# MultiChannelLdc2.net
KiCad netlist of a schematic drawn in Altium Designer
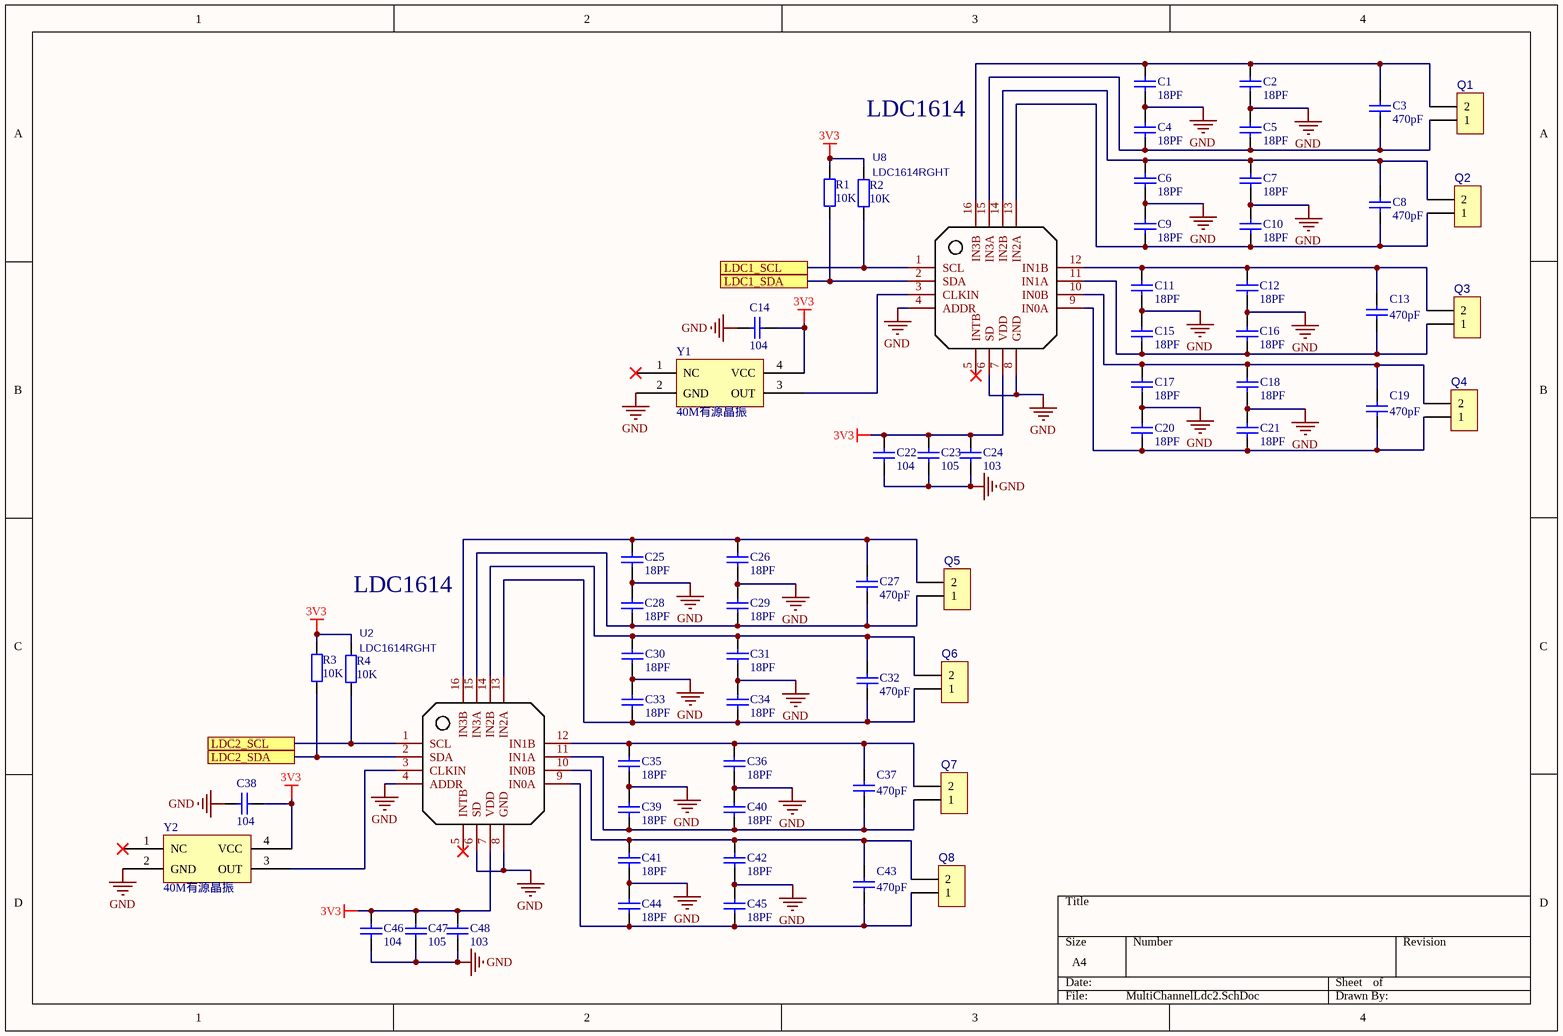
[diagram p0: MultiChannelLdc2.SchDoc]

(export (version "E")
  (design (tool "Eeschema 10.0.6"))
  (components
    (comp (ref "C1")
      (value "18PF")
      (footprint "C0603_L")
      (description "Capacitor")
      (fields (field (name "PUBLISHER") "Altium Limited"))
      (libsource (lib "STM32F103C8T6") (part "Cap"))
    )
    (comp (ref "C2")
      (value "18PF")
      (footprint "C0603_L")
      (description "Capacitor")
      (fields (field (name "PUBLISHER") "Altium Limited"))
      (libsource (lib "STM32F103C8T6") (part "Cap"))
    )
    (comp (ref "C3")
      (value "470pF")
      (footprint "C0603_L")
      (description "Capacitor")
      (fields (field (name "PUBLISHER") "Altium Limited"))
      (libsource (lib "STM32F103C8T6") (part "Cap"))
    )
    (comp (ref "C4")
      (value "18PF")
      (footprint "C0603_L")
      (description "Capacitor")
      (fields (field (name "PUBLISHER") "Altium Limited"))
      (libsource (lib "STM32F103C8T6") (part "Cap"))
    )
    (comp (ref "C5")
      (value "18PF")
      (footprint "C0603_L")
      (description "Capacitor")
      (fields (field (name "PUBLISHER") "Altium Limited"))
      (libsource (lib "STM32F103C8T6") (part "Cap"))
    )
    (comp (ref "C6")
      (value "18PF")
      (footprint "C0603_L")
      (description "Capacitor")
      (fields (field (name "PUBLISHER") "Altium Limited"))
      (libsource (lib "STM32F103C8T6") (part "Cap"))
    )
    (comp (ref "C7")
      (value "18PF")
      (footprint "C0603_L")
      (description "Capacitor")
      (fields (field (name "PUBLISHER") "Altium Limited"))
      (libsource (lib "STM32F103C8T6") (part "Cap"))
    )
    (comp (ref "C8")
      (value "470pF")
      (footprint "C0603_L")
      (description "Capacitor")
      (fields (field (name "PUBLISHER") "Altium Limited"))
      (libsource (lib "STM32F103C8T6") (part "Cap"))
    )
    (comp (ref "C9")
      (value "18PF")
      (footprint "C0603_L")
      (description "Capacitor")
      (fields (field (name "PUBLISHER") "Altium Limited"))
      (libsource (lib "STM32F103C8T6") (part "Cap"))
    )
    (comp (ref "C10")
      (value "18PF")
      (footprint "C0603_L")
      (description "Capacitor")
      (fields (field (name "PUBLISHER") "Altium Limited"))
      (libsource (lib "STM32F103C8T6") (part "Cap"))
    )
    (comp (ref "C11")
      (value "18PF")
      (footprint "C0603_L")
      (description "Capacitor")
      (fields (field (name "PUBLISHER") "Altium Limited"))
      (libsource (lib "STM32F103C8T6") (part "Cap"))
    )
    (comp (ref "C12")
      (value "18PF")
      (footprint "C0603_L")
      (description "Capacitor")
      (fields (field (name "PUBLISHER") "Altium Limited"))
      (libsource (lib "STM32F103C8T6") (part "Cap"))
    )
    (comp (ref "C13")
      (value "470pF")
      (footprint "C0603_L")
      (description "Capacitor")
      (fields (field (name "PUBLISHER") "Altium Limited"))
      (libsource (lib "STM32F103C8T6") (part "Cap"))
    )
    (comp (ref "C14")
      (value "104")
      (footprint "C0603_L")
      (description "贴片电容/MLCC电容")
      (libsource (lib "Ldc1614_Pro") (part "C"))
    )
    (comp (ref "C15")
      (value "18PF")
      (footprint "C0603_L")
      (description "Capacitor")
      (fields (field (name "PUBLISHER") "Altium Limited"))
      (libsource (lib "STM32F103C8T6") (part "Cap"))
    )
    (comp (ref "C16")
      (value "18PF")
      (footprint "C0603_L")
      (description "Capacitor")
      (fields (field (name "PUBLISHER") "Altium Limited"))
      (libsource (lib "STM32F103C8T6") (part "Cap"))
    )
    (comp (ref "C17")
      (value "18PF")
      (footprint "C0603_L")
      (description "Capacitor")
      (fields (field (name "PUBLISHER") "Altium Limited"))
      (libsource (lib "STM32F103C8T6") (part "Cap"))
    )
    (comp (ref "C18")
      (value "18PF")
      (footprint "C0603_L")
      (description "Capacitor")
      (fields (field (name "PUBLISHER") "Altium Limited"))
      (libsource (lib "STM32F103C8T6") (part "Cap"))
    )
    (comp (ref "C19")
      (value "470pF")
      (footprint "C0603_L")
      (description "Capacitor")
      (fields (field (name "PUBLISHER") "Altium Limited"))
      (libsource (lib "STM32F103C8T6") (part "Cap"))
    )
    (comp (ref "C20")
      (value "18PF")
      (footprint "C0603_L")
      (description "Capacitor")
      (fields (field (name "PUBLISHER") "Altium Limited"))
      (libsource (lib "STM32F103C8T6") (part "Cap"))
    )
    (comp (ref "C21")
      (value "18PF")
      (footprint "C0603_L")
      (description "Capacitor")
      (fields (field (name "PUBLISHER") "Altium Limited"))
      (libsource (lib "STM32F103C8T6") (part "Cap"))
    )
    (comp (ref "C22")
      (value "104")
      (footprint "C0603_L")
      (description "Capacitor")
      (fields (field (name "PUBLISHER") "Altium Limited"))
      (libsource (lib "STM32F103C8T6") (part "Cap"))
    )
    (comp (ref "C23")
      (value "105")
      (footprint "C0603_L")
      (description "Capacitor")
      (fields (field (name "PUBLISHER") "Altium Limited"))
      (libsource (lib "STM32F103C8T6") (part "Cap"))
    )
    (comp (ref "C24")
      (value "103")
      (footprint "C0603_L")
      (description "Capacitor")
      (fields (field (name "PUBLISHER") "Altium Limited"))
      (libsource (lib "STM32F103C8T6") (part "Cap"))
    )
    (comp (ref "C25")
      (value "18PF")
      (footprint "C0603_L")
      (description "Capacitor")
      (fields (field (name "PUBLISHER") "Altium Limited"))
      (libsource (lib "STM32F103C8T6") (part "Cap"))
    )
    (comp (ref "C26")
      (value "18PF")
      (footprint "C0603_L")
      (description "Capacitor")
      (fields (field (name "PUBLISHER") "Altium Limited"))
      (libsource (lib "STM32F103C8T6") (part "Cap"))
    )
    (comp (ref "C27")
      (value "470pF")
      (footprint "C0603_L")
      (description "Capacitor")
      (fields (field (name "PUBLISHER") "Altium Limited"))
      (libsource (lib "STM32F103C8T6") (part "Cap"))
    )
    (comp (ref "C28")
      (value "18PF")
      (footprint "C0603_L")
      (description "Capacitor")
      (fields (field (name "PUBLISHER") "Altium Limited"))
      (libsource (lib "STM32F103C8T6") (part "Cap"))
    )
    (comp (ref "C29")
      (value "18PF")
      (footprint "C0603_L")
      (description "Capacitor")
      (fields (field (name "PUBLISHER") "Altium Limited"))
      (libsource (lib "STM32F103C8T6") (part "Cap"))
    )
    (comp (ref "C30")
      (value "18PF")
      (footprint "C0603_L")
      (description "Capacitor")
      (fields (field (name "PUBLISHER") "Altium Limited"))
      (libsource (lib "STM32F103C8T6") (part "Cap"))
    )
    (comp (ref "C31")
      (value "18PF")
      (footprint "C0603_L")
      (description "Capacitor")
      (fields (field (name "PUBLISHER") "Altium Limited"))
      (libsource (lib "STM32F103C8T6") (part "Cap"))
    )
    (comp (ref "C32")
      (value "470pF")
      (footprint "C0603_L")
      (description "Capacitor")
      (fields (field (name "PUBLISHER") "Altium Limited"))
      (libsource (lib "STM32F103C8T6") (part "Cap"))
    )
    (comp (ref "C33")
      (value "18PF")
      (footprint "C0603_L")
      (description "Capacitor")
      (fields (field (name "PUBLISHER") "Altium Limited"))
      (libsource (lib "STM32F103C8T6") (part "Cap"))
    )
    (comp (ref "C34")
      (value "18PF")
      (footprint "C0603_L")
      (description "Capacitor")
      (fields (field (name "PUBLISHER") "Altium Limited"))
      (libsource (lib "STM32F103C8T6") (part "Cap"))
    )
    (comp (ref "C35")
      (value "18PF")
      (footprint "C0603_L")
      (description "Capacitor")
      (fields (field (name "PUBLISHER") "Altium Limited"))
      (libsource (lib "STM32F103C8T6") (part "Cap"))
    )
    (comp (ref "C36")
      (value "18PF")
      (footprint "C0603_L")
      (description "Capacitor")
      (fields (field (name "PUBLISHER") "Altium Limited"))
      (libsource (lib "STM32F103C8T6") (part "Cap"))
    )
    (comp (ref "C37")
      (value "470pF")
      (footprint "C0603_L")
      (description "Capacitor")
      (fields (field (name "PUBLISHER") "Altium Limited"))
      (libsource (lib "STM32F103C8T6") (part "Cap"))
    )
    (comp (ref "C38")
      (value "104")
      (footprint "C0603_L")
      (description "贴片电容/MLCC电容")
      (libsource (lib "Ldc1614_Pro") (part "C"))
    )
    (comp (ref "C39")
      (value "18PF")
      (footprint "C0603_L")
      (description "Capacitor")
      (fields (field (name "PUBLISHER") "Altium Limited"))
      (libsource (lib "STM32F103C8T6") (part "Cap"))
    )
    (comp (ref "C40")
      (value "18PF")
      (footprint "C0603_L")
      (description "Capacitor")
      (fields (field (name "PUBLISHER") "Altium Limited"))
      (libsource (lib "STM32F103C8T6") (part "Cap"))
    )
    (comp (ref "C41")
      (value "18PF")
      (footprint "C0603_L")
      (description "Capacitor")
      (fields (field (name "PUBLISHER") "Altium Limited"))
      (libsource (lib "STM32F103C8T6") (part "Cap"))
    )
    (comp (ref "C42")
      (value "18PF")
      (footprint "C0603_L")
      (description "Capacitor")
      (fields (field (name "PUBLISHER") "Altium Limited"))
      (libsource (lib "STM32F103C8T6") (part "Cap"))
    )
    (comp (ref "C43")
      (value "470pF")
      (footprint "C0603_L")
      (description "Capacitor")
      (fields (field (name "PUBLISHER") "Altium Limited"))
      (libsource (lib "STM32F103C8T6") (part "Cap"))
    )
    (comp (ref "C44")
      (value "18PF")
      (footprint "C0603_L")
      (description "Capacitor")
      (fields (field (name "PUBLISHER") "Altium Limited"))
      (libsource (lib "STM32F103C8T6") (part "Cap"))
    )
    (comp (ref "C45")
      (value "18PF")
      (footprint "C0603_L")
      (description "Capacitor")
      (fields (field (name "PUBLISHER") "Altium Limited"))
      (libsource (lib "STM32F103C8T6") (part "Cap"))
    )
    (comp (ref "C46")
      (value "104")
      (footprint "C0603_L")
      (description "Capacitor")
      (fields (field (name "PUBLISHER") "Altium Limited"))
      (libsource (lib "STM32F103C8T6") (part "Cap"))
    )
    (comp (ref "C47")
      (value "105")
      (footprint "C0603_L")
      (description "Capacitor")
      (fields (field (name "PUBLISHER") "Altium Limited"))
      (libsource (lib "STM32F103C8T6") (part "Cap"))
    )
    (comp (ref "C48")
      (value "103")
      (footprint "C0603_L")
      (description "Capacitor")
      (fields (field (name "PUBLISHER") "Altium Limited"))
      (libsource (lib "STM32F103C8T6") (part "Cap"))
    )
    (comp (ref "Q1")
      (value "~")
      (footprint "座子")
      (description "Connector")
      (libsource (lib "*") (part "CON2"))
    )
    (comp (ref "Q2")
      (value "~")
      (footprint "座子")
      (description "Connector")
      (libsource (lib "*") (part "CON2"))
    )
    (comp (ref "Q3")
      (value "~")
      (footprint "座子")
      (description "Connector")
      (libsource (lib "*") (part "CON2"))
    )
    (comp (ref "Q4")
      (value "~")
      (footprint "座子")
      (description "Connector")
      (libsource (lib "*") (part "CON2"))
    )
    (comp (ref "Q5")
      (value "~")
      (footprint "座子")
      (description "Connector")
      (libsource (lib "*") (part "CON2"))
    )
    (comp (ref "Q6")
      (value "~")
      (footprint "座子")
      (description "Connector")
      (libsource (lib "*") (part "CON2"))
    )
    (comp (ref "Q7")
      (value "~")
      (footprint "座子")
      (description "Connector")
      (libsource (lib "*") (part "CON2"))
    )
    (comp (ref "Q8")
      (value "~")
      (footprint "座子")
      (description "Connector")
      (libsource (lib "*") (part "CON2"))
    )
    (comp (ref "R1")
      (value "10K")
      (footprint "R0603_L")
      (description "Resistor")
      (fields (field (name "Comment") "Res2") (field (name "PUBLISHER") "Altium Limited"))
      (libsource (lib "LDC") (part "Res2"))
    )
    (comp (ref "R2")
      (value "10K")
      (footprint "R0603_L")
      (description "Resistor")
      (fields (field (name "Comment") "Res2") (field (name "PUBLISHER") "Altium Limited"))
      (libsource (lib "Miscellaneous Devices") (part "Res2"))
    )
    (comp (ref "R3")
      (value "10K")
      (footprint "R0603_L")
      (description "Resistor")
      (fields (field (name "Comment") "Res2") (field (name "PUBLISHER") "Altium Limited"))
      (libsource (lib "LDC") (part "Res2"))
    )
    (comp (ref "R4")
      (value "10K")
      (footprint "R0603_L")
      (description "Resistor")
      (fields (field (name "Comment") "Res2") (field (name "PUBLISHER") "Altium Limited"))
      (libsource (lib "Miscellaneous Devices") (part "Res2"))
    )
    (comp (ref "U2")
      (value "LDC1614RGHT")
      (footprint "W-QFN-16")
      (fields
        (field (name "BOM_MANUFACTURER PART") "LDC1314RGHT")
        (field (name "BOM_SUPPLIER PART") "C80399")
      )
      (libsource (lib "LDC1614") (part "LDC1614RGHT"))
    )
    (comp (ref "U8")
      (value "LDC1614RGHT")
      (footprint "W-QFN-16")
      (fields
        (field (name "BOM_MANUFACTURER PART") "LDC1314RGHT")
        (field (name "BOM_SUPPLIER PART") "C80399")
      )
      (libsource (lib "LDC1614") (part "LDC1614RGHT"))
    )
    (comp (ref "Y1") (value "40M有源晶振") (footprint "SMD3225") (libsource (lib "其他常用元件类") (part "有源晶振")))
    (comp (ref "Y2") (value "40M有源晶振") (footprint "SMD3225") (libsource (lib "其他常用元件类") (part "有源晶振")))
  )
  (nets
    (net (code "1") (name "/LDC1_SCL") (class "Default")
      (node (ref "U8") (pin "1") (pinfunction "SCL_1") (pintype "passive"))
    )
    (net (code "2") (name "/LDC1_SDA") (class "Default")
      (node (ref "R1") (pin "1") (pinfunction "1_1") (pintype "passive"))
      (node (ref "U8") (pin "2") (pinfunction "SDA_2") (pintype "passive"))
    )
    (net (code "3") (name "/LDC2_SCL") (class "Default")
      (node (ref "U2") (pin "1") (pinfunction "SCL_1") (pintype "passive"))
    )
    (net (code "4") (name "/LDC2_SDA") (class "Default")
      (node (ref "R3") (pin "1") (pinfunction "1_1") (pintype "passive"))
      (node (ref "U2") (pin "2") (pinfunction "SDA_2") (pintype "passive"))
    )
    (net (code "5") (name "3V3") (class "Default")
      (node (ref "C14") (pin "1") (pinfunction "1_1") (pintype "passive"))
      (node (ref "C22") (pin "1") (pinfunction "1_1") (pintype "passive"))
      (node (ref "C23") (pin "1") (pinfunction "1_1") (pintype "passive"))
      (node (ref "C24") (pin "1") (pinfunction "1_1") (pintype "passive"))
      (node (ref "C38") (pin "1") (pinfunction "1_1") (pintype "passive"))
      (node (ref "C46") (pin "1") (pinfunction "1_1") (pintype "passive"))
      (node (ref "C47") (pin "1") (pinfunction "1_1") (pintype "passive"))
      (node (ref "C48") (pin "1") (pinfunction "1_1") (pintype "passive"))
      (node (ref "R1") (pin "2") (pinfunction "2_2") (pintype "passive"))
      (node (ref "R2") (pin "1") (pinfunction "1_1") (pintype "passive"))
      (node (ref "R3") (pin "2") (pinfunction "2_2") (pintype "passive"))
      (node (ref "R4") (pin "1") (pinfunction "1_1") (pintype "passive"))
      (node (ref "U2") (pin "7") (pinfunction "VDD_7") (pintype "passive"))
      (node (ref "U8") (pin "7") (pinfunction "VDD_7") (pintype "passive"))
      (node (ref "Y1") (pin "4") (pinfunction "VCC_4") (pintype "passive"))
      (node (ref "Y2") (pin "4") (pinfunction "VCC_4") (pintype "passive"))
    )
    (net (code "6") (name "GND") (class "Default")
      (node (ref "C1") (pin "2") (pinfunction "2_2") (pintype "passive"))
      (node (ref "C10") (pin "1") (pinfunction "1_1") (pintype "passive"))
      (node (ref "C11") (pin "2") (pinfunction "2_2") (pintype "passive"))
      (node (ref "C12") (pin "2") (pinfunction "2_2") (pintype "passive"))
      (node (ref "C14") (pin "2") (pinfunction "2_2") (pintype "passive"))
      (node (ref "C15") (pin "1") (pinfunction "1_1") (pintype "passive"))
      (node (ref "C16") (pin "1") (pinfunction "1_1") (pintype "passive"))
      (node (ref "C17") (pin "2") (pinfunction "2_2") (pintype "passive"))
      (node (ref "C18") (pin "2") (pinfunction "2_2") (pintype "passive"))
      (node (ref "C2") (pin "2") (pinfunction "2_2") (pintype "passive"))
      (node (ref "C20") (pin "1") (pinfunction "1_1") (pintype "passive"))
      (node (ref "C21") (pin "1") (pinfunction "1_1") (pintype "passive"))
      (node (ref "C22") (pin "2") (pinfunction "2_2") (pintype "passive"))
      (node (ref "C23") (pin "2") (pinfunction "2_2") (pintype "passive"))
      (node (ref "C24") (pin "2") (pinfunction "2_2") (pintype "passive"))
      (node (ref "C25") (pin "2") (pinfunction "2_2") (pintype "passive"))
      (node (ref "C26") (pin "2") (pinfunction "2_2") (pintype "passive"))
      (node (ref "C28") (pin "1") (pinfunction "1_1") (pintype "passive"))
      (node (ref "C29") (pin "1") (pinfunction "1_1") (pintype "passive"))
      (node (ref "C30") (pin "2") (pinfunction "2_2") (pintype "passive"))
      (node (ref "C31") (pin "2") (pinfunction "2_2") (pintype "passive"))
      (node (ref "C33") (pin "1") (pinfunction "1_1") (pintype "passive"))
      (node (ref "C34") (pin "1") (pinfunction "1_1") (pintype "passive"))
      (node (ref "C35") (pin "2") (pinfunction "2_2") (pintype "passive"))
      (node (ref "C36") (pin "2") (pinfunction "2_2") (pintype "passive"))
      (node (ref "C38") (pin "2") (pinfunction "2_2") (pintype "passive"))
      (node (ref "C39") (pin "1") (pinfunction "1_1") (pintype "passive"))
      (node (ref "C4") (pin "1") (pinfunction "1_1") (pintype "passive"))
      (node (ref "C40") (pin "1") (pinfunction "1_1") (pintype "passive"))
      (node (ref "C41") (pin "2") (pinfunction "2_2") (pintype "passive"))
      (node (ref "C42") (pin "2") (pinfunction "2_2") (pintype "passive"))
      (node (ref "C44") (pin "1") (pinfunction "1_1") (pintype "passive"))
      (node (ref "C45") (pin "1") (pinfunction "1_1") (pintype "passive"))
      (node (ref "C46") (pin "2") (pinfunction "2_2") (pintype "passive"))
      (node (ref "C47") (pin "2") (pinfunction "2_2") (pintype "passive"))
      (node (ref "C48") (pin "2") (pinfunction "2_2") (pintype "passive"))
      (node (ref "C5") (pin "1") (pinfunction "1_1") (pintype "passive"))
      (node (ref "C6") (pin "2") (pinfunction "2_2") (pintype "passive"))
      (node (ref "C7") (pin "2") (pinfunction "2_2") (pintype "passive"))
      (node (ref "C9") (pin "1") (pinfunction "1_1") (pintype "passive"))
      (node (ref "U2") (pin "4") (pinfunction "ADDR_4") (pintype "passive"))
      (node (ref "U2") (pin "6") (pinfunction "SD_6") (pintype "passive"))
      (node (ref "U2") (pin "8") (pinfunction "GND_8") (pintype "passive"))
      (node (ref "U8") (pin "4") (pinfunction "ADDR_4") (pintype "passive"))
      (node (ref "U8") (pin "6") (pinfunction "SD_6") (pintype "passive"))
      (node (ref "U8") (pin "8") (pinfunction "GND_8") (pintype "passive"))
      (node (ref "Y1") (pin "2") (pinfunction "GND_2") (pintype "passive"))
      (node (ref "Y2") (pin "2") (pinfunction "GND_2") (pintype "passive"))
    )
    (net (code "7") (name "Net-(U2-CLKIN)") (class "Default")
      (node (ref "U2") (pin "3") (pinfunction "CLKIN_3") (pintype "passive"))
      (node (ref "Y2") (pin "3") (pinfunction "OUT_3") (pintype "passive"))
    )
    (net (code "8") (name "Net-(U2-IN0A)") (class "Default")
      (node (ref "C43") (pin "1") (pinfunction "1_1") (pintype "passive"))
      (node (ref "C44") (pin "2") (pinfunction "2_2") (pintype "passive"))
      (node (ref "C45") (pin "2") (pinfunction "2_2") (pintype "passive"))
      (node (ref "Q8") (pin "1") (pinfunction "1_1") (pintype "passive"))
      (node (ref "U2") (pin "9") (pinfunction "IN0A_9") (pintype "passive"))
    )
    (net (code "9") (name "Net-(U2-IN0B)") (class "Default")
      (node (ref "C41") (pin "1") (pinfunction "1_1") (pintype "passive"))
      (node (ref "C42") (pin "1") (pinfunction "1_1") (pintype "passive"))
      (node (ref "C43") (pin "2") (pinfunction "2_2") (pintype "passive"))
      (node (ref "Q8") (pin "2") (pinfunction "2_2") (pintype "passive"))
      (node (ref "U2") (pin "10") (pinfunction "IN0B_10") (pintype "passive"))
    )
    (net (code "10") (name "Net-(U2-IN1A)") (class "Default")
      (node (ref "C37") (pin "1") (pinfunction "1_1") (pintype "passive"))
      (node (ref "C39") (pin "2") (pinfunction "2_2") (pintype "passive"))
      (node (ref "C40") (pin "2") (pinfunction "2_2") (pintype "passive"))
      (node (ref "Q7") (pin "1") (pinfunction "1_1") (pintype "passive"))
      (node (ref "U2") (pin "11") (pinfunction "IN1A_11") (pintype "passive"))
    )
    (net (code "11") (name "Net-(U2-IN1B)") (class "Default")
      (node (ref "C35") (pin "1") (pinfunction "1_1") (pintype "passive"))
      (node (ref "C36") (pin "1") (pinfunction "1_1") (pintype "passive"))
      (node (ref "C37") (pin "2") (pinfunction "2_2") (pintype "passive"))
      (node (ref "Q7") (pin "2") (pinfunction "2_2") (pintype "passive"))
      (node (ref "U2") (pin "12") (pinfunction "IN1B_12") (pintype "passive"))
    )
    (net (code "12") (name "Net-(U2-IN2A)") (class "Default")
      (node (ref "C32") (pin "1") (pinfunction "1_1") (pintype "passive"))
      (node (ref "C33") (pin "2") (pinfunction "2_2") (pintype "passive"))
      (node (ref "C34") (pin "2") (pinfunction "2_2") (pintype "passive"))
      (node (ref "Q6") (pin "1") (pinfunction "1_1") (pintype "passive"))
      (node (ref "U2") (pin "13") (pinfunction "IN2A_13") (pintype "passive"))
    )
    (net (code "13") (name "Net-(U2-IN2B)") (class "Default")
      (node (ref "C30") (pin "1") (pinfunction "1_1") (pintype "passive"))
      (node (ref "C31") (pin "1") (pinfunction "1_1") (pintype "passive"))
      (node (ref "C32") (pin "2") (pinfunction "2_2") (pintype "passive"))
      (node (ref "Q6") (pin "2") (pinfunction "2_2") (pintype "passive"))
      (node (ref "U2") (pin "14") (pinfunction "IN2B_14") (pintype "passive"))
    )
    (net (code "14") (name "Net-(U2-IN3A)") (class "Default")
      (node (ref "C27") (pin "1") (pinfunction "1_1") (pintype "passive"))
      (node (ref "C28") (pin "2") (pinfunction "2_2") (pintype "passive"))
      (node (ref "C29") (pin "2") (pinfunction "2_2") (pintype "passive"))
      (node (ref "Q5") (pin "1") (pinfunction "1_1") (pintype "passive"))
      (node (ref "U2") (pin "15") (pinfunction "IN3A_15") (pintype "passive"))
    )
    (net (code "15") (name "Net-(U2-IN3B)") (class "Default")
      (node (ref "C25") (pin "1") (pinfunction "1_1") (pintype "passive"))
      (node (ref "C26") (pin "1") (pinfunction "1_1") (pintype "passive"))
      (node (ref "C27") (pin "2") (pinfunction "2_2") (pintype "passive"))
      (node (ref "Q5") (pin "2") (pinfunction "2_2") (pintype "passive"))
      (node (ref "U2") (pin "16") (pinfunction "IN3B_16") (pintype "passive"))
    )
    (net (code "16") (name "Net-(U8-CLKIN)") (class "Default")
      (node (ref "U8") (pin "3") (pinfunction "CLKIN_3") (pintype "passive"))
      (node (ref "Y1") (pin "3") (pinfunction "OUT_3") (pintype "passive"))
    )
    (net (code "17") (name "Net-(U8-IN0A)") (class "Default")
      (node (ref "C19") (pin "1") (pinfunction "1_1") (pintype "passive"))
      (node (ref "C20") (pin "2") (pinfunction "2_2") (pintype "passive"))
      (node (ref "C21") (pin "2") (pinfunction "2_2") (pintype "passive"))
      (node (ref "Q4") (pin "1") (pinfunction "1_1") (pintype "passive"))
      (node (ref "U8") (pin "9") (pinfunction "IN0A_9") (pintype "passive"))
    )
    (net (code "18") (name "Net-(U8-IN0B)") (class "Default")
      (node (ref "C17") (pin "1") (pinfunction "1_1") (pintype "passive"))
      (node (ref "C18") (pin "1") (pinfunction "1_1") (pintype "passive"))
      (node (ref "C19") (pin "2") (pinfunction "2_2") (pintype "passive"))
      (node (ref "Q4") (pin "2") (pinfunction "2_2") (pintype "passive"))
      (node (ref "U8") (pin "10") (pinfunction "IN0B_10") (pintype "passive"))
    )
    (net (code "19") (name "Net-(U8-IN1A)") (class "Default")
      (node (ref "C13") (pin "1") (pinfunction "1_1") (pintype "passive"))
      (node (ref "C15") (pin "2") (pinfunction "2_2") (pintype "passive"))
      (node (ref "C16") (pin "2") (pinfunction "2_2") (pintype "passive"))
      (node (ref "Q3") (pin "1") (pinfunction "1_1") (pintype "passive"))
      (node (ref "U8") (pin "11") (pinfunction "IN1A_11") (pintype "passive"))
    )
    (net (code "20") (name "Net-(U8-IN1B)") (class "Default")
      (node (ref "C11") (pin "1") (pinfunction "1_1") (pintype "passive"))
      (node (ref "C12") (pin "1") (pinfunction "1_1") (pintype "passive"))
      (node (ref "C13") (pin "2") (pinfunction "2_2") (pintype "passive"))
      (node (ref "Q3") (pin "2") (pinfunction "2_2") (pintype "passive"))
      (node (ref "U8") (pin "12") (pinfunction "IN1B_12") (pintype "passive"))
    )
    (net (code "21") (name "Net-(U8-IN2A)") (class "Default")
      (node (ref "C10") (pin "2") (pinfunction "2_2") (pintype "passive"))
      (node (ref "C8") (pin "1") (pinfunction "1_1") (pintype "passive"))
      (node (ref "C9") (pin "2") (pinfunction "2_2") (pintype "passive"))
      (node (ref "Q2") (pin "1") (pinfunction "1_1") (pintype "passive"))
      (node (ref "U8") (pin "13") (pinfunction "IN2A_13") (pintype "passive"))
    )
    (net (code "22") (name "Net-(U8-IN2B)") (class "Default")
      (node (ref "C6") (pin "1") (pinfunction "1_1") (pintype "passive"))
      (node (ref "C7") (pin "1") (pinfunction "1_1") (pintype "passive"))
      (node (ref "C8") (pin "2") (pinfunction "2_2") (pintype "passive"))
      (node (ref "Q2") (pin "2") (pinfunction "2_2") (pintype "passive"))
      (node (ref "U8") (pin "14") (pinfunction "IN2B_14") (pintype "passive"))
    )
    (net (code "23") (name "Net-(U8-IN3A)") (class "Default")
      (node (ref "C3") (pin "1") (pinfunction "1_1") (pintype "passive"))
      (node (ref "C4") (pin "2") (pinfunction "2_2") (pintype "passive"))
      (node (ref "C5") (pin "2") (pinfunction "2_2") (pintype "passive"))
      (node (ref "Q1") (pin "1") (pinfunction "1_1") (pintype "passive"))
      (node (ref "U8") (pin "15") (pinfunction "IN3A_15") (pintype "passive"))
    )
    (net (code "24") (name "Net-(U8-IN3B)") (class "Default")
      (node (ref "C1") (pin "1") (pinfunction "1_1") (pintype "passive"))
      (node (ref "C2") (pin "1") (pinfunction "1_1") (pintype "passive"))
      (node (ref "C3") (pin "2") (pinfunction "2_2") (pintype "passive"))
      (node (ref "Q1") (pin "2") (pinfunction "2_2") (pintype "passive"))
      (node (ref "U8") (pin "16") (pinfunction "IN3B_16") (pintype "passive"))
    )
    (net (code "25") (name "unconnected-(R2-Pad2)") (class "Default")
      (node (ref "R2") (pin "2") (pinfunction "2_2") (pintype "passive"))
    )
    (net (code "26") (name "unconnected-(R4-Pad2)") (class "Default")
      (node (ref "R4") (pin "2") (pinfunction "2_2") (pintype "passive"))
    )
    (net (code "27") (name "unconnected-(U2-INTB-Pad5)") (class "Default")
      (node (ref "U2") (pin "5") (pinfunction "INTB_5") (pintype "passive+no_connect"))
    )
    (net (code "28") (name "unconnected-(U8-INTB-Pad5)") (class "Default")
      (node (ref "U8") (pin "5") (pinfunction "INTB_5") (pintype "passive+no_connect"))
    )
    (net (code "29") (name "unconnected-(Y1-NC-Pad1)") (class "Default")
      (node (ref "Y1") (pin "1") (pinfunction "NC_1") (pintype "passive+no_connect"))
    )
    (net (code "30") (name "unconnected-(Y2-NC-Pad1)") (class "Default")
      (node (ref "Y2") (pin "1") (pinfunction "NC_1") (pintype "passive+no_connect"))
    )
  )
)
